# growPi_v2_0.net
KiCad netlist of a schematic drawn in EAGLE
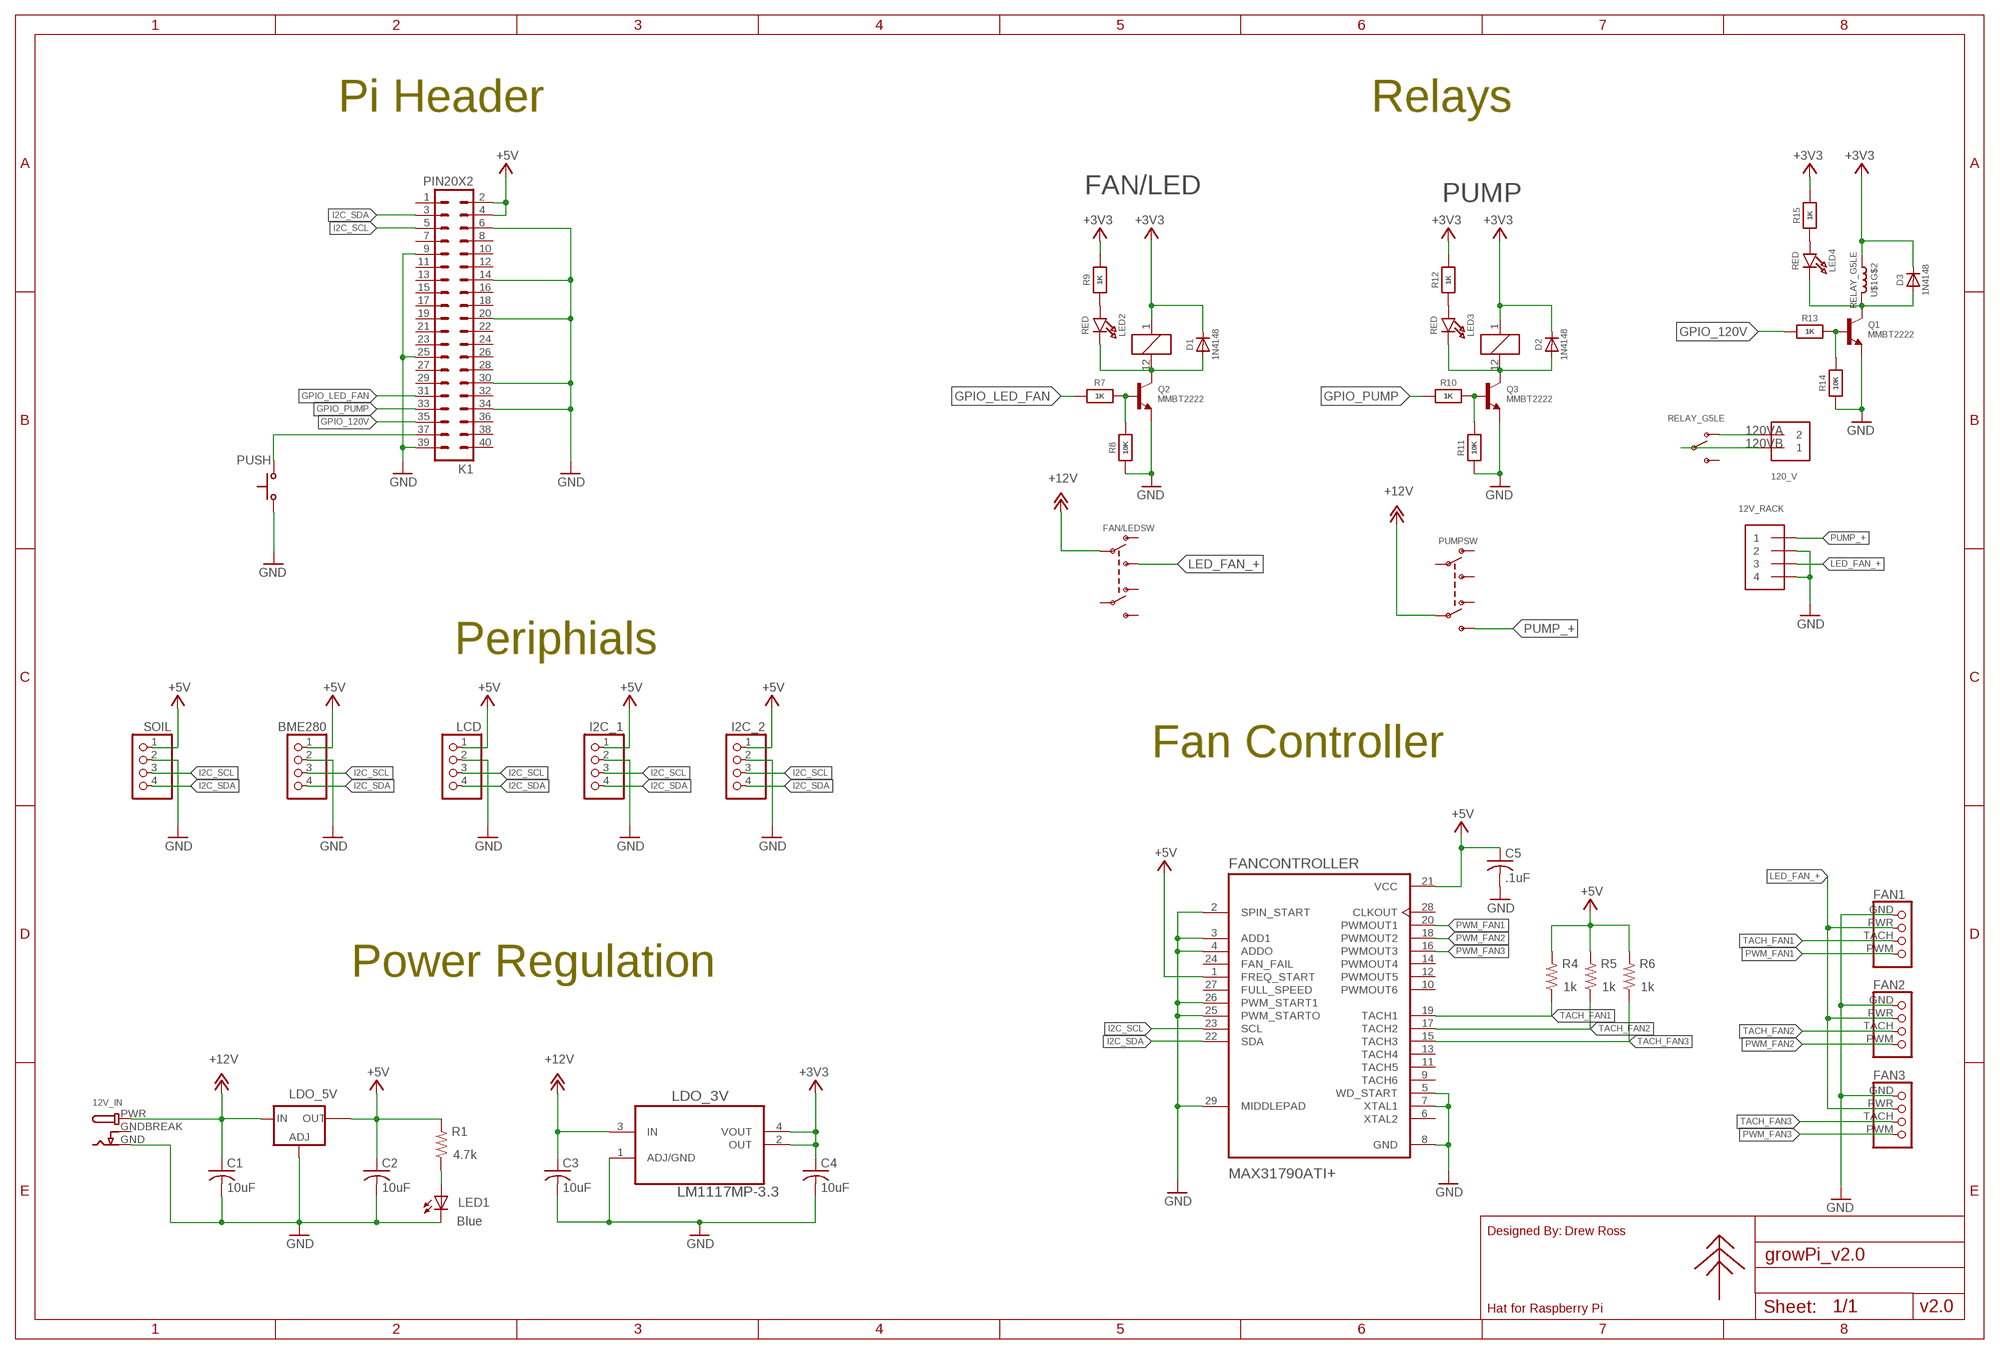
[diagram p0: schematic, sheet 1]

(export (version "E")
  (design (tool "Eeschema 10.0.6"))
  (components
    (comp (ref "12V_IN")
      (value "DCBARRELSMT_CORRECT")
      (footprint "eagle-import:DCJACK_2MM_SMT")
      (libsource (lib "eagle-import") (part "DCBARRELSMT_CORRECT"))
    )
    (comp (ref "12V_RACK")
      (value "TERMBLOCK_1X4-5.0MM")
      (footprint "eagle-import:TERMBLOCK_1X4-5.0MM")
      (libsource (lib "eagle-import") (part "TERMBLOCK_1X4-5.0MM"))
    )
    (comp (ref "120_V")
      (value "TERMBLOCK_1X2-5.0MM")
      (footprint "eagle-import:TERMBLOCK_1X2-5.0MM")
      (libsource (lib "eagle-import") (part "TERMBLOCK_1X2-5.0MM"))
    )
    (comp (ref "BME280")
      (value "PINHD-1X4")
      (footprint "eagle-import:1X04")
      (libsource (lib "eagle-import") (part "PINHD-1X4"))
    )
    (comp (ref "C1")
      (value "10uF")
      (footprint "eagle-import:C0603")
      (libsource (lib "eagle-import") (part "C-USC0603"))
    )
    (comp (ref "C2")
      (value "10uF")
      (footprint "eagle-import:C0603")
      (libsource (lib "eagle-import") (part "C-USC0603"))
    )
    (comp (ref "C3")
      (value "10uF")
      (footprint "eagle-import:C0603")
      (libsource (lib "eagle-import") (part "C-USC0603"))
    )
    (comp (ref "C4")
      (value "10uF")
      (footprint "eagle-import:C0603")
      (libsource (lib "eagle-import") (part "C-USC0603"))
    )
    (comp (ref "C5")
      (value ".1uF")
      (footprint "eagle-import:C0603")
      (libsource (lib "eagle-import") (part "C-USC0603"))
    )
    (comp (ref "D1")
      (value "1N4148")
      (footprint "eagle-import:SOD-323")
      (libsource (lib "eagle-import") (part "DIODESOD-323"))
    )
    (comp (ref "D2")
      (value "1N4148")
      (footprint "eagle-import:SOD-323")
      (libsource (lib "eagle-import") (part "DIODESOD-323"))
    )
    (comp (ref "D3")
      (value "1N4148")
      (footprint "eagle-import:SOD-323")
      (libsource (lib "eagle-import") (part "DIODESOD-323"))
    )
    (comp (ref "FAN/LED")
      (value "RELAY_NONLATCHING-EE2NUH")
      (footprint "eagle-import:RELAY_EE2_NOLATCH")
      (libsource (lib "eagle-import") (part "RELAY_NONLATCHING-EE2NUH"))
    )
    (comp (ref "FAN1")
      (value "4PIN-MOLEX-FAN")
      (footprint "eagle-import:4PIN-FAN-HEADER")
      (libsource (lib "eagle-import") (part "4PIN-MOLEX-FAN"))
    )
    (comp (ref "FAN2")
      (value "4PIN-MOLEX-FAN")
      (footprint "eagle-import:4PIN-FAN-HEADER")
      (libsource (lib "eagle-import") (part "4PIN-MOLEX-FAN"))
    )
    (comp (ref "FAN3")
      (value "4PIN-MOLEX-FAN")
      (footprint "eagle-import:4PIN-FAN-HEADER")
      (libsource (lib "eagle-import") (part "4PIN-MOLEX-FAN"))
    )
    (comp (ref "FANCONTROLLER")
      (value "MAX31790ATI+")
      (footprint "eagle-import:QFN40P400X400X80-29N")
      (fields (field (name "MF") "Maxim Integrated"))
      (libsource (lib "eagle-import") (part "MAX31790ATI+"))
    )
    (comp (ref "I2C_1")
      (value "PINHD-1X4")
      (footprint "eagle-import:1X04")
      (libsource (lib "eagle-import") (part "PINHD-1X4"))
    )
    (comp (ref "I2C_2")
      (value "PINHD-1X4")
      (footprint "eagle-import:1X04")
      (libsource (lib "eagle-import") (part "PINHD-1X4"))
    )
    (comp (ref "K1")
      (value "PIN20X2")
      (footprint "eagle-import:PIN_20X2")
      (libsource (lib "eagle-import") (part "PIN20X2"))
    )
    (comp (ref "LCD")
      (value "PINHD-1X4")
      (footprint "eagle-import:1X04")
      (libsource (lib "eagle-import") (part "PINHD-1X4"))
    )
    (comp (ref "LDO_3V")
      (value "LM1117MP-3.3")
      (footprint "eagle-import:SOT230P696X180-4N")
      (fields (field (name "MF") "Texas Instruments"))
      (libsource (lib "eagle-import") (part "LM1117MP-3.3"))
    )
    (comp (ref "LDO_5V")
      (value "LM1084IS")
      (footprint "eagle-import:TO263")
      (libsource (lib "eagle-import") (part "LM1084IS"))
    )
    (comp (ref "LED1")
      (value "Blue")
      (footprint "eagle-import:CHIPLED_0603")
      (libsource (lib "eagle-import") (part "LEDCHIPLED_0603"))
    )
    (comp (ref "LED2")
      (value "RED")
      (footprint "eagle-import:CHIPLED_0603_NOOUTLINE")
      (libsource (lib "eagle-import") (part "LED0603_NOOUTLINE"))
    )
    (comp (ref "LED3")
      (value "RED")
      (footprint "eagle-import:CHIPLED_0603_NOOUTLINE")
      (libsource (lib "eagle-import") (part "LED0603_NOOUTLINE"))
    )
    (comp (ref "LED4")
      (value "RED")
      (footprint "eagle-import:CHIPLED_0603_NOOUTLINE")
      (libsource (lib "eagle-import") (part "LED0603_NOOUTLINE"))
    )
    (comp (ref "PLANTLOGO")
      (value "PLANTLOGO")
      (footprint "eagle-import:PLANT")
      (libsource (lib "eagle-import") (part "PLANTLOGO"))
    )
    (comp (ref "PUMP")
      (value "RELAY_NONLATCHING-EE2NUH")
      (footprint "eagle-import:RELAY_EE2_NOLATCH")
      (libsource (lib "eagle-import") (part "RELAY_NONLATCHING-EE2NUH"))
    )
    (comp (ref "PUSH")
      (value "PTS645SSMTR")
      (footprint "eagle-import:PTS645-SMD")
      (libsource (lib "eagle-import") (part "PTS645S???SMTR"))
    )
    (comp (ref "Q1")
      (value "MMBT2222")
      (footprint "eagle-import:SOT23-R")
      (libsource (lib "eagle-import") (part "TRANSISTOR_NPN"))
    )
    (comp (ref "Q2")
      (value "MMBT2222")
      (footprint "eagle-import:SOT23-R")
      (libsource (lib "eagle-import") (part "TRANSISTOR_NPN"))
    )
    (comp (ref "Q3")
      (value "MMBT2222")
      (footprint "eagle-import:SOT23-R")
      (libsource (lib "eagle-import") (part "TRANSISTOR_NPN"))
    )
    (comp (ref "R1")
      (value "4.7k")
      (footprint "eagle-import:R0603")
      (libsource (lib "eagle-import") (part "R-US_R0603"))
    )
    (comp (ref "R4")
      (value "1k")
      (footprint "eagle-import:R0603")
      (libsource (lib "eagle-import") (part "R-US_R0603"))
    )
    (comp (ref "R5")
      (value "1k")
      (footprint "eagle-import:R0603")
      (libsource (lib "eagle-import") (part "R-US_R0603"))
    )
    (comp (ref "R6")
      (value "1k")
      (footprint "eagle-import:R0603")
      (libsource (lib "eagle-import") (part "R-US_R0603"))
    )
    (comp (ref "R7")
      (value "1K")
      (footprint "eagle-import:0603-NO")
      (libsource (lib "eagle-import") (part "RESISTOR_0603_NOOUT"))
    )
    (comp (ref "R8")
      (value "10K")
      (footprint "eagle-import:0603-NO")
      (libsource (lib "eagle-import") (part "RESISTOR_0603_NOOUT"))
    )
    (comp (ref "R9")
      (value "1K")
      (footprint "eagle-import:0603-NO")
      (libsource (lib "eagle-import") (part "RESISTOR_0603_NOOUT"))
    )
    (comp (ref "R10")
      (value "1K")
      (footprint "eagle-import:0603-NO")
      (libsource (lib "eagle-import") (part "RESISTOR_0603_NOOUT"))
    )
    (comp (ref "R11")
      (value "10K")
      (footprint "eagle-import:0603-NO")
      (libsource (lib "eagle-import") (part "RESISTOR_0603_NOOUT"))
    )
    (comp (ref "R12")
      (value "1K")
      (footprint "eagle-import:0603-NO")
      (libsource (lib "eagle-import") (part "RESISTOR_0603_NOOUT"))
    )
    (comp (ref "R13")
      (value "1K")
      (footprint "eagle-import:0603-NO")
      (libsource (lib "eagle-import") (part "RESISTOR_0603_NOOUT"))
    )
    (comp (ref "R14")
      (value "10K")
      (footprint "eagle-import:0603-NO")
      (libsource (lib "eagle-import") (part "RESISTOR_0603_NOOUT"))
    )
    (comp (ref "R15")
      (value "1K")
      (footprint "eagle-import:0603-NO")
      (libsource (lib "eagle-import") (part "RESISTOR_0603_NOOUT"))
    )
    (comp (ref "SOIL")
      (value "PINHD-1X4")
      (footprint "eagle-import:1X04")
      (libsource (lib "eagle-import") (part "PINHD-1X4"))
    )
    (comp (ref "U$1")
      (value "RELAY_G5LE")
      (footprint "eagle-import:RELAY_G5LE-1")
      (libsource (lib "eagle-import") (part "RELAY_G5LE"))
    )
  )
  (nets
    (net (code "1") (name "+3V3") (class "Default")
      (node (ref "C4") (pin "1") (pinfunction "1_1") (pintype "passive"))
      (node (ref "D1") (pin "C") (pinfunction "C_C") (pintype "passive"))
      (node (ref "D2") (pin "C") (pinfunction "C_C") (pintype "passive"))
      (node (ref "D3") (pin "C") (pinfunction "C_C") (pintype "passive"))
      (node (ref "FAN/LED") (pin "1") (pinfunction "1_1") (pintype "passive"))
      (node (ref "LDO_3V") (pin "2") (pinfunction "OUT_2") (pintype "output"))
      (node (ref "LDO_3V") (pin "4") (pinfunction "VOUT_4") (pintype "output"))
      (node (ref "PUMP") (pin "1") (pinfunction "1_1") (pintype "passive"))
      (node (ref "R12") (pin "2") (pinfunction "2_2") (pintype "passive"))
      (node (ref "R15") (pin "2") (pinfunction "2_2") (pintype "passive"))
      (node (ref "R9") (pin "2") (pinfunction "2_2") (pintype "passive"))
      (node (ref "U$1") (pin "2") (pinfunction "1_2") (pintype "passive"))
    )
    (net (code "2") (name "+5V") (class "Default")
      (node (ref "BME280") (pin "1") (pinfunction "1_1") (pintype "passive"))
      (node (ref "C2") (pin "1") (pinfunction "1_1") (pintype "passive"))
      (node (ref "C5") (pin "1") (pinfunction "1_1") (pintype "passive"))
      (node (ref "FANCONTROLLER") (pin "1") (pinfunction "FREQ_START_1") (pintype "bidirectional"))
      (node (ref "FANCONTROLLER") (pin "21") (pinfunction "VCC_21") (pintype "power_in"))
      (node (ref "I2C_1") (pin "1") (pinfunction "1_1") (pintype "passive"))
      (node (ref "I2C_2") (pin "1") (pinfunction "1_1") (pintype "passive"))
      (node (ref "K1") (pin "2") (pinfunction "2_2") (pintype "passive"))
      (node (ref "K1") (pin "4") (pinfunction "4_4") (pintype "passive"))
      (node (ref "LCD") (pin "1") (pinfunction "1_1") (pintype "passive"))
      (node (ref "LDO_5V") (pin "2") (pinfunction "OUT_2") (pintype "passive"))
      (node (ref "R1") (pin "2") (pinfunction "2_2") (pintype "passive"))
      (node (ref "R4") (pin "2") (pinfunction "2_2") (pintype "passive"))
      (node (ref "R5") (pin "2") (pinfunction "2_2") (pintype "passive"))
      (node (ref "R6") (pin "2") (pinfunction "2_2") (pintype "passive"))
      (node (ref "SOIL") (pin "1") (pinfunction "1_1") (pintype "passive"))
    )
    (net (code "3") (name "+12V") (class "Default")
      (node (ref "12V_IN") (pin "PWR") (pinfunction "PWR_PWR") (pintype "power_in"))
      (node (ref "C1") (pin "1") (pinfunction "1_1") (pintype "passive"))
      (node (ref "C3") (pin "1") (pinfunction "1_1") (pintype "passive"))
      (node (ref "FAN/LED") (pin "9") (pinfunction "P1_9") (pintype "passive"))
      (node (ref "LDO_3V") (pin "3") (pinfunction "IN_3") (pintype "input"))
      (node (ref "LDO_5V") (pin "3") (pinfunction "IN_3") (pintype "input"))
      (node (ref "PUMP") (pin "4") (pinfunction "P2_4") (pintype "passive"))
    )
    (net (code "4") (name "/120VA") (class "Default")
      (node (ref "120_V") (pin "2") (pinfunction "2_2") (pintype "passive"))
      (node (ref "U$1") (pin "3") (pinfunction "O_3") (pintype "passive"))
    )
    (net (code "5") (name "/120VB") (class "Default")
      (node (ref "120_V") (pin "1") (pinfunction "1_1") (pintype "passive"))
      (node (ref "U$1") (pin "1") (pinfunction "P_1") (pintype "passive"))
    )
    (net (code "6") (name "/GNDBREAK") (class "Default")
      (node (ref "12V_IN") (pin "GNDBREAK") (pinfunction "GNDBREAK_GNDBREAK") (pintype "power_in"))
    )
    (net (code "7") (name "GND") (class "Default")
      (node (ref "12V_IN") (pin "GND") (pinfunction "GND_GND") (pintype "power_in"))
      (node (ref "12V_RACK") (pin "2") (pinfunction "2_2") (pintype "passive"))
      (node (ref "12V_RACK") (pin "4") (pinfunction "4_4") (pintype "passive"))
      (node (ref "BME280") (pin "2") (pinfunction "2_2") (pintype "passive"))
      (node (ref "C1") (pin "2") (pinfunction "2_2") (pintype "passive"))
      (node (ref "C2") (pin "2") (pinfunction "2_2") (pintype "passive"))
      (node (ref "C3") (pin "2") (pinfunction "2_2") (pintype "passive"))
      (node (ref "C4") (pin "2") (pinfunction "2_2") (pintype "passive"))
      (node (ref "C5") (pin "2") (pinfunction "2_2") (pintype "passive"))
      (node (ref "FAN1") (pin "GND") (pinfunction "1_GND") (pintype "passive"))
      (node (ref "FAN2") (pin "GND") (pinfunction "1_GND") (pintype "passive"))
      (node (ref "FAN3") (pin "GND") (pinfunction "1_GND") (pintype "passive"))
      (node (ref "FANCONTROLLER") (pin "2") (pinfunction "SPIN_START_2") (pintype "input"))
      (node (ref "FANCONTROLLER") (pin "25") (pinfunction "PWM_STARTO_25") (pintype "bidirectional"))
      (node (ref "FANCONTROLLER") (pin "26") (pinfunction "PWM_START1_26") (pintype "bidirectional"))
      (node (ref "FANCONTROLLER") (pin "29") (pinfunction "MIDDLEPAD_29") (pintype "bidirectional"))
      (node (ref "FANCONTROLLER") (pin "3") (pinfunction "ADD1_3") (pintype "bidirectional"))
      (node (ref "FANCONTROLLER") (pin "4") (pinfunction "ADDO_4") (pintype "bidirectional"))
      (node (ref "FANCONTROLLER") (pin "5") (pinfunction "WD_START_5") (pintype "bidirectional"))
      (node (ref "FANCONTROLLER") (pin "7") (pinfunction "XTAL1_7") (pintype "bidirectional"))
      (node (ref "FANCONTROLLER") (pin "8") (pinfunction "GND_8") (pintype "power_in"))
      (node (ref "I2C_1") (pin "2") (pinfunction "2_2") (pintype "passive"))
      (node (ref "I2C_2") (pin "2") (pinfunction "2_2") (pintype "passive"))
      (node (ref "K1") (pin "14") (pinfunction "14_14") (pintype "passive"))
      (node (ref "K1") (pin "20") (pinfunction "20_20") (pintype "passive"))
      (node (ref "K1") (pin "25") (pinfunction "25_25") (pintype "passive"))
      (node (ref "K1") (pin "30") (pinfunction "30_30") (pintype "passive"))
      (node (ref "K1") (pin "34") (pinfunction "34_34") (pintype "passive"))
      (node (ref "K1") (pin "39") (pinfunction "39_39") (pintype "passive"))
      (node (ref "K1") (pin "6") (pinfunction "6_6") (pintype "passive"))
      (node (ref "K1") (pin "9") (pinfunction "9_9") (pintype "passive"))
      (node (ref "LCD") (pin "2") (pinfunction "2_2") (pintype "passive"))
      (node (ref "LDO_3V") (pin "1") (pinfunction "ADJ/GND_1") (pintype "passive"))
      (node (ref "LDO_5V") (pin "1") (pinfunction "ADJ_1") (pintype "input"))
      (node (ref "LED1") (pin "C") (pinfunction "C_C") (pintype "passive"))
      (node (ref "PUSH") (pin "1") (pinfunction "P_1") (pintype "passive"))
      (node (ref "PUSH") (pin "2") (pinfunction "P_2") (pintype "passive"))
      (node (ref "Q1") (pin "2") (pinfunction "E_2") (pintype "passive"))
      (node (ref "Q2") (pin "2") (pinfunction "E_2") (pintype "passive"))
      (node (ref "Q3") (pin "2") (pinfunction "E_2") (pintype "passive"))
      (node (ref "R11") (pin "1") (pinfunction "1_1") (pintype "passive"))
      (node (ref "R14") (pin "1") (pinfunction "1_1") (pintype "passive"))
      (node (ref "R8") (pin "1") (pinfunction "1_1") (pintype "passive"))
      (node (ref "SOIL") (pin "2") (pinfunction "2_2") (pintype "passive"))
    )
    (net (code "8") (name "GPIO_120V") (class "Default")
      (node (ref "K1") (pin "35") (pinfunction "35_35") (pintype "passive"))
      (node (ref "R13") (pin "1") (pinfunction "1_1") (pintype "passive"))
    )
    (net (code "9") (name "GPIO_LED_FAN") (class "Default")
      (node (ref "K1") (pin "31") (pinfunction "31_31") (pintype "passive"))
      (node (ref "R7") (pin "1") (pinfunction "1_1") (pintype "passive"))
    )
    (net (code "10") (name "GPIO_PUMP") (class "Default")
      (node (ref "K1") (pin "33") (pinfunction "33_33") (pintype "passive"))
      (node (ref "R10") (pin "1") (pinfunction "1_1") (pintype "passive"))
    )
    (net (code "11") (name "I2C_SCL") (class "Default")
      (node (ref "BME280") (pin "3") (pinfunction "3_3") (pintype "passive"))
      (node (ref "FANCONTROLLER") (pin "23") (pinfunction "SCL_23") (pintype "bidirectional"))
      (node (ref "I2C_1") (pin "3") (pinfunction "3_3") (pintype "passive"))
      (node (ref "I2C_2") (pin "3") (pinfunction "3_3") (pintype "passive"))
      (node (ref "K1") (pin "5") (pinfunction "5_5") (pintype "passive"))
      (node (ref "LCD") (pin "3") (pinfunction "3_3") (pintype "passive"))
      (node (ref "SOIL") (pin "3") (pinfunction "3_3") (pintype "passive"))
    )
    (net (code "12") (name "I2C_SDA") (class "Default")
      (node (ref "BME280") (pin "4") (pinfunction "4_4") (pintype "passive"))
      (node (ref "FANCONTROLLER") (pin "22") (pinfunction "SDA_22") (pintype "bidirectional"))
      (node (ref "I2C_1") (pin "4") (pinfunction "4_4") (pintype "passive"))
      (node (ref "I2C_2") (pin "4") (pinfunction "4_4") (pintype "passive"))
      (node (ref "K1") (pin "3") (pinfunction "3_3") (pintype "passive"))
      (node (ref "LCD") (pin "4") (pinfunction "4_4") (pintype "passive"))
      (node (ref "SOIL") (pin "4") (pinfunction "4_4") (pintype "passive"))
    )
    (net (code "13") (name "LED_FAN_+") (class "Default")
      (node (ref "12V_RACK") (pin "3") (pinfunction "3_3") (pintype "passive"))
      (node (ref "FAN/LED") (pin "8") (pinfunction "S1_8") (pintype "passive"))
      (node (ref "FAN1") (pin "PWR") (pinfunction "2_PWR") (pintype "passive"))
      (node (ref "FAN2") (pin "PWR") (pinfunction "2_PWR") (pintype "passive"))
      (node (ref "FAN3") (pin "PWR") (pinfunction "2_PWR") (pintype "passive"))
    )
    (net (code "14") (name "Net-(FAN/LEDA-2)") (class "Default")
      (node (ref "D1") (pin "A") (pinfunction "A_A") (pintype "passive"))
      (node (ref "FAN/LED") (pin "12") (pinfunction "2_12") (pintype "passive"))
      (node (ref "LED2") (pin "C") (pinfunction "C_C") (pintype "passive"))
      (node (ref "Q2") (pin "3") (pinfunction "C_3") (pintype "passive"))
    )
    (net (code "15") (name "Net-(K1-Pad37)") (class "Default")
      (node (ref "K1") (pin "37") (pinfunction "37_37") (pintype "passive"))
      (node (ref "PUSH") (pin "3") (pinfunction "S_3") (pintype "passive"))
      (node (ref "PUSH") (pin "4") (pinfunction "S_4") (pintype "passive"))
    )
    (net (code "16") (name "Net-(LED1-PadA)") (class "Default")
      (node (ref "LED1") (pin "A") (pinfunction "A_A") (pintype "passive"))
      (node (ref "R1") (pin "1") (pinfunction "1_1") (pintype "passive"))
    )
    (net (code "17") (name "Net-(LED2-PadA)") (class "Default")
      (node (ref "LED2") (pin "A") (pinfunction "A_A") (pintype "passive"))
      (node (ref "R9") (pin "1") (pinfunction "1_1") (pintype "passive"))
    )
    (net (code "18") (name "Net-(LED3-PadA)") (class "Default")
      (node (ref "LED3") (pin "A") (pinfunction "A_A") (pintype "passive"))
      (node (ref "R12") (pin "1") (pinfunction "1_1") (pintype "passive"))
    )
    (net (code "19") (name "Net-(LED4-PadA)") (class "Default")
      (node (ref "LED4") (pin "A") (pinfunction "A_A") (pintype "passive"))
      (node (ref "R15") (pin "1") (pinfunction "1_1") (pintype "passive"))
    )
    (net (code "20") (name "Net-(PUMPA-2)") (class "Default")
      (node (ref "D2") (pin "A") (pinfunction "A_A") (pintype "passive"))
      (node (ref "LED3") (pin "C") (pinfunction "C_C") (pintype "passive"))
      (node (ref "PUMP") (pin "12") (pinfunction "2_12") (pintype "passive"))
      (node (ref "Q3") (pin "3") (pinfunction "C_3") (pintype "passive"))
    )
    (net (code "21") (name "Net-(Q1-B)") (class "Default")
      (node (ref "Q1") (pin "1") (pinfunction "B_1") (pintype "passive"))
      (node (ref "R13") (pin "2") (pinfunction "2_2") (pintype "passive"))
      (node (ref "R14") (pin "2") (pinfunction "2_2") (pintype "passive"))
    )
    (net (code "22") (name "Net-(Q1-C)") (class "Default")
      (node (ref "D3") (pin "A") (pinfunction "A_A") (pintype "passive"))
      (node (ref "LED4") (pin "C") (pinfunction "C_C") (pintype "passive"))
      (node (ref "Q1") (pin "3") (pinfunction "C_3") (pintype "passive"))
      (node (ref "U$1") (pin "5") (pinfunction "2_5") (pintype "passive"))
    )
    (net (code "23") (name "Net-(Q2-B)") (class "Default")
      (node (ref "Q2") (pin "1") (pinfunction "B_1") (pintype "passive"))
      (node (ref "R7") (pin "2") (pinfunction "2_2") (pintype "passive"))
      (node (ref "R8") (pin "2") (pinfunction "2_2") (pintype "passive"))
    )
    (net (code "24") (name "Net-(Q3-B)") (class "Default")
      (node (ref "Q3") (pin "1") (pinfunction "B_1") (pintype "passive"))
      (node (ref "R10") (pin "2") (pinfunction "2_2") (pintype "passive"))
      (node (ref "R11") (pin "2") (pinfunction "2_2") (pintype "passive"))
    )
    (net (code "25") (name "PUMP_+") (class "Default")
      (node (ref "12V_RACK") (pin "1") (pinfunction "1_1") (pintype "passive"))
      (node (ref "PUMP") (pin "5") (pinfunction "S2_5") (pintype "passive"))
    )
    (net (code "26") (name "PWM_FAN1") (class "Default")
      (node (ref "FAN1") (pin "PWM") (pinfunction "4_PWM") (pintype "passive"))
      (node (ref "FANCONTROLLER") (pin "20") (pinfunction "PWMOUT1_20") (pintype "output"))
    )
    (net (code "27") (name "PWM_FAN2") (class "Default")
      (node (ref "FAN2") (pin "PWM") (pinfunction "4_PWM") (pintype "passive"))
      (node (ref "FANCONTROLLER") (pin "18") (pinfunction "PWMOUT2_18") (pintype "output"))
    )
    (net (code "28") (name "PWM_FAN3") (class "Default")
      (node (ref "FAN3") (pin "PWM") (pinfunction "4_PWM") (pintype "passive"))
      (node (ref "FANCONTROLLER") (pin "16") (pinfunction "PWMOUT3_16") (pintype "output"))
    )
    (net (code "29") (name "TACH_FAN1") (class "Default")
      (node (ref "FAN1") (pin "TACH") (pinfunction "3_TACH") (pintype "passive"))
      (node (ref "FANCONTROLLER") (pin "19") (pinfunction "TACH1_19") (pintype "bidirectional"))
      (node (ref "R4") (pin "1") (pinfunction "1_1") (pintype "passive"))
    )
    (net (code "30") (name "TACH_FAN2") (class "Default")
      (node (ref "FAN2") (pin "TACH") (pinfunction "3_TACH") (pintype "passive"))
      (node (ref "FANCONTROLLER") (pin "17") (pinfunction "TACH2_17") (pintype "bidirectional"))
      (node (ref "R5") (pin "1") (pinfunction "1_1") (pintype "passive"))
    )
    (net (code "31") (name "TACH_FAN3") (class "Default")
      (node (ref "FAN3") (pin "TACH") (pinfunction "3_TACH") (pintype "passive"))
      (node (ref "FANCONTROLLER") (pin "15") (pinfunction "TACH3_15") (pintype "bidirectional"))
      (node (ref "R6") (pin "1") (pinfunction "1_1") (pintype "passive"))
    )
    (net (code "32") (name "unconnected-(FAN/LEDB-O1-Pad10)") (class "Default")
      (node (ref "FAN/LED") (pin "10") (pinfunction "O1_10") (pintype "passive"))
    )
    (net (code "33") (name "unconnected-(FAN/LEDB-O2-Pad3)") (class "Default")
      (node (ref "FAN/LED") (pin "3") (pinfunction "O2_3") (pintype "passive"))
    )
    (net (code "34") (name "unconnected-(FAN/LEDB-P2-Pad4)") (class "Default")
      (node (ref "FAN/LED") (pin "4") (pinfunction "P2_4") (pintype "passive"))
    )
    (net (code "35") (name "unconnected-(FAN/LEDB-S2-Pad5)") (class "Default")
      (node (ref "FAN/LED") (pin "5") (pinfunction "S2_5") (pintype "passive"))
    )
    (net (code "36") (name "unconnected-(FANCONTROLLER-CLKOUT-Pad28)") (class "Default")
      (node (ref "FANCONTROLLER") (pin "28") (pinfunction "CLKOUT_28") (pintype "output"))
    )
    (net (code "37") (name "unconnected-(FANCONTROLLER-FAN_FAIL-Pad24)") (class "Default")
      (node (ref "FANCONTROLLER") (pin "24") (pinfunction "FAN_FAIL_24") (pintype "bidirectional"))
    )
    (net (code "38") (name "unconnected-(FANCONTROLLER-FULL_SPEED-Pad27)") (class "Default")
      (node (ref "FANCONTROLLER") (pin "27") (pinfunction "FULL_SPEED_27") (pintype "bidirectional"))
    )
    (net (code "39") (name "unconnected-(FANCONTROLLER-PWMOUT4-Pad14)") (class "Default")
      (node (ref "FANCONTROLLER") (pin "14") (pinfunction "PWMOUT4_14") (pintype "output"))
    )
    (net (code "40") (name "unconnected-(FANCONTROLLER-PWMOUT5-Pad12)") (class "Default")
      (node (ref "FANCONTROLLER") (pin "12") (pinfunction "PWMOUT5_12") (pintype "output"))
    )
    (net (code "41") (name "unconnected-(FANCONTROLLER-PWMOUT6-Pad10)") (class "Default")
      (node (ref "FANCONTROLLER") (pin "10") (pinfunction "PWMOUT6_10") (pintype "output"))
    )
    (net (code "42") (name "unconnected-(FANCONTROLLER-TACH4-Pad13)") (class "Default")
      (node (ref "FANCONTROLLER") (pin "13") (pinfunction "TACH4_13") (pintype "bidirectional"))
    )
    (net (code "43") (name "unconnected-(FANCONTROLLER-TACH5-Pad11)") (class "Default")
      (node (ref "FANCONTROLLER") (pin "11") (pinfunction "TACH5_11") (pintype "bidirectional"))
    )
    (net (code "44") (name "unconnected-(FANCONTROLLER-TACH6-Pad9)") (class "Default")
      (node (ref "FANCONTROLLER") (pin "9") (pinfunction "TACH6_9") (pintype "bidirectional"))
    )
    (net (code "45") (name "unconnected-(FANCONTROLLER-XTAL2-Pad6)") (class "Default")
      (node (ref "FANCONTROLLER") (pin "6") (pinfunction "XTAL2_6") (pintype "bidirectional"))
    )
    (net (code "46") (name "unconnected-(K1-Pad1)") (class "Default")
      (node (ref "K1") (pin "1") (pinfunction "1_1") (pintype "passive"))
    )
    (net (code "47") (name "unconnected-(K1-Pad7)") (class "Default")
      (node (ref "K1") (pin "7") (pinfunction "7_7") (pintype "passive"))
    )
    (net (code "48") (name "unconnected-(K1-Pad8)") (class "Default")
      (node (ref "K1") (pin "8") (pinfunction "8_8") (pintype "passive"))
    )
    (net (code "49") (name "unconnected-(K1-Pad10)") (class "Default")
      (node (ref "K1") (pin "10") (pinfunction "10_10") (pintype "passive"))
    )
    (net (code "50") (name "unconnected-(K1-Pad11)") (class "Default")
      (node (ref "K1") (pin "11") (pinfunction "11_11") (pintype "passive"))
    )
    (net (code "51") (name "unconnected-(K1-Pad12)") (class "Default")
      (node (ref "K1") (pin "12") (pinfunction "12_12") (pintype "passive"))
    )
    (net (code "52") (name "unconnected-(K1-Pad13)") (class "Default")
      (node (ref "K1") (pin "13") (pinfunction "13_13") (pintype "passive"))
    )
    (net (code "53") (name "unconnected-(K1-Pad15)") (class "Default")
      (node (ref "K1") (pin "15") (pinfunction "15_15") (pintype "passive"))
    )
    (net (code "54") (name "unconnected-(K1-Pad16)") (class "Default")
      (node (ref "K1") (pin "16") (pinfunction "16_16") (pintype "passive"))
    )
    (net (code "55") (name "unconnected-(K1-Pad17)") (class "Default")
      (node (ref "K1") (pin "17") (pinfunction "17_17") (pintype "passive"))
    )
    (net (code "56") (name "unconnected-(K1-Pad18)") (class "Default")
      (node (ref "K1") (pin "18") (pinfunction "18_18") (pintype "passive"))
    )
    (net (code "57") (name "unconnected-(K1-Pad19)") (class "Default")
      (node (ref "K1") (pin "19") (pinfunction "19_19") (pintype "passive"))
    )
    (net (code "58") (name "unconnected-(K1-Pad21)") (class "Default")
      (node (ref "K1") (pin "21") (pinfunction "21_21") (pintype "passive"))
    )
    (net (code "59") (name "unconnected-(K1-Pad22)") (class "Default")
      (node (ref "K1") (pin "22") (pinfunction "22_22") (pintype "passive"))
    )
    (net (code "60") (name "unconnected-(K1-Pad23)") (class "Default")
      (node (ref "K1") (pin "23") (pinfunction "23_23") (pintype "passive"))
    )
    (net (code "61") (name "unconnected-(K1-Pad24)") (class "Default")
      (node (ref "K1") (pin "24") (pinfunction "24_24") (pintype "passive"))
    )
    (net (code "62") (name "unconnected-(K1-Pad26)") (class "Default")
      (node (ref "K1") (pin "26") (pinfunction "26_26") (pintype "passive"))
    )
    (net (code "63") (name "unconnected-(K1-Pad27)") (class "Default")
      (node (ref "K1") (pin "27") (pinfunction "27_27") (pintype "passive"))
    )
    (net (code "64") (name "unconnected-(K1-Pad28)") (class "Default")
      (node (ref "K1") (pin "28") (pinfunction "28_28") (pintype "passive"))
    )
    (net (code "65") (name "unconnected-(K1-Pad29)") (class "Default")
      (node (ref "K1") (pin "29") (pinfunction "29_29") (pintype "passive"))
    )
    (net (code "66") (name "unconnected-(K1-Pad32)") (class "Default")
      (node (ref "K1") (pin "32") (pinfunction "32_32") (pintype "passive"))
    )
    (net (code "67") (name "unconnected-(K1-Pad36)") (class "Default")
      (node (ref "K1") (pin "36") (pinfunction "36_36") (pintype "passive"))
    )
    (net (code "68") (name "unconnected-(K1-Pad38)") (class "Default")
      (node (ref "K1") (pin "38") (pinfunction "38_38") (pintype "passive"))
    )
    (net (code "69") (name "unconnected-(K1-Pad40)") (class "Default")
      (node (ref "K1") (pin "40") (pinfunction "40_40") (pintype "passive"))
    )
    (net (code "70") (name "unconnected-(LDO_5V-OUT4-Pad4)") (class "Default")
      (node (ref "LDO_5V") (pin "4") (pinfunction "OUT4_4") (pintype "passive"))
    )
    (net (code "71") (name "unconnected-(PUMPB-O1-Pad10)") (class "Default")
      (node (ref "PUMP") (pin "10") (pinfunction "O1_10") (pintype "passive"))
    )
    (net (code "72") (name "unconnected-(PUMPB-O2-Pad3)") (class "Default")
      (node (ref "PUMP") (pin "3") (pinfunction "O2_3") (pintype "passive"))
    )
    (net (code "73") (name "unconnected-(PUMPB-P1-Pad9)") (class "Default")
      (node (ref "PUMP") (pin "9") (pinfunction "P1_9") (pintype "passive"))
    )
    (net (code "74") (name "unconnected-(PUMPB-S1-Pad8)") (class "Default")
      (node (ref "PUMP") (pin "8") (pinfunction "S1_8") (pintype "passive"))
    )
    (net (code "75") (name "unconnected-(U$1A-S-Pad4)") (class "Default")
      (node (ref "U$1") (pin "4") (pinfunction "S_4") (pintype "passive"))
    )
  )
)
